# MC60.net
KiCad netlist of a schematic drawn in Altium Designer
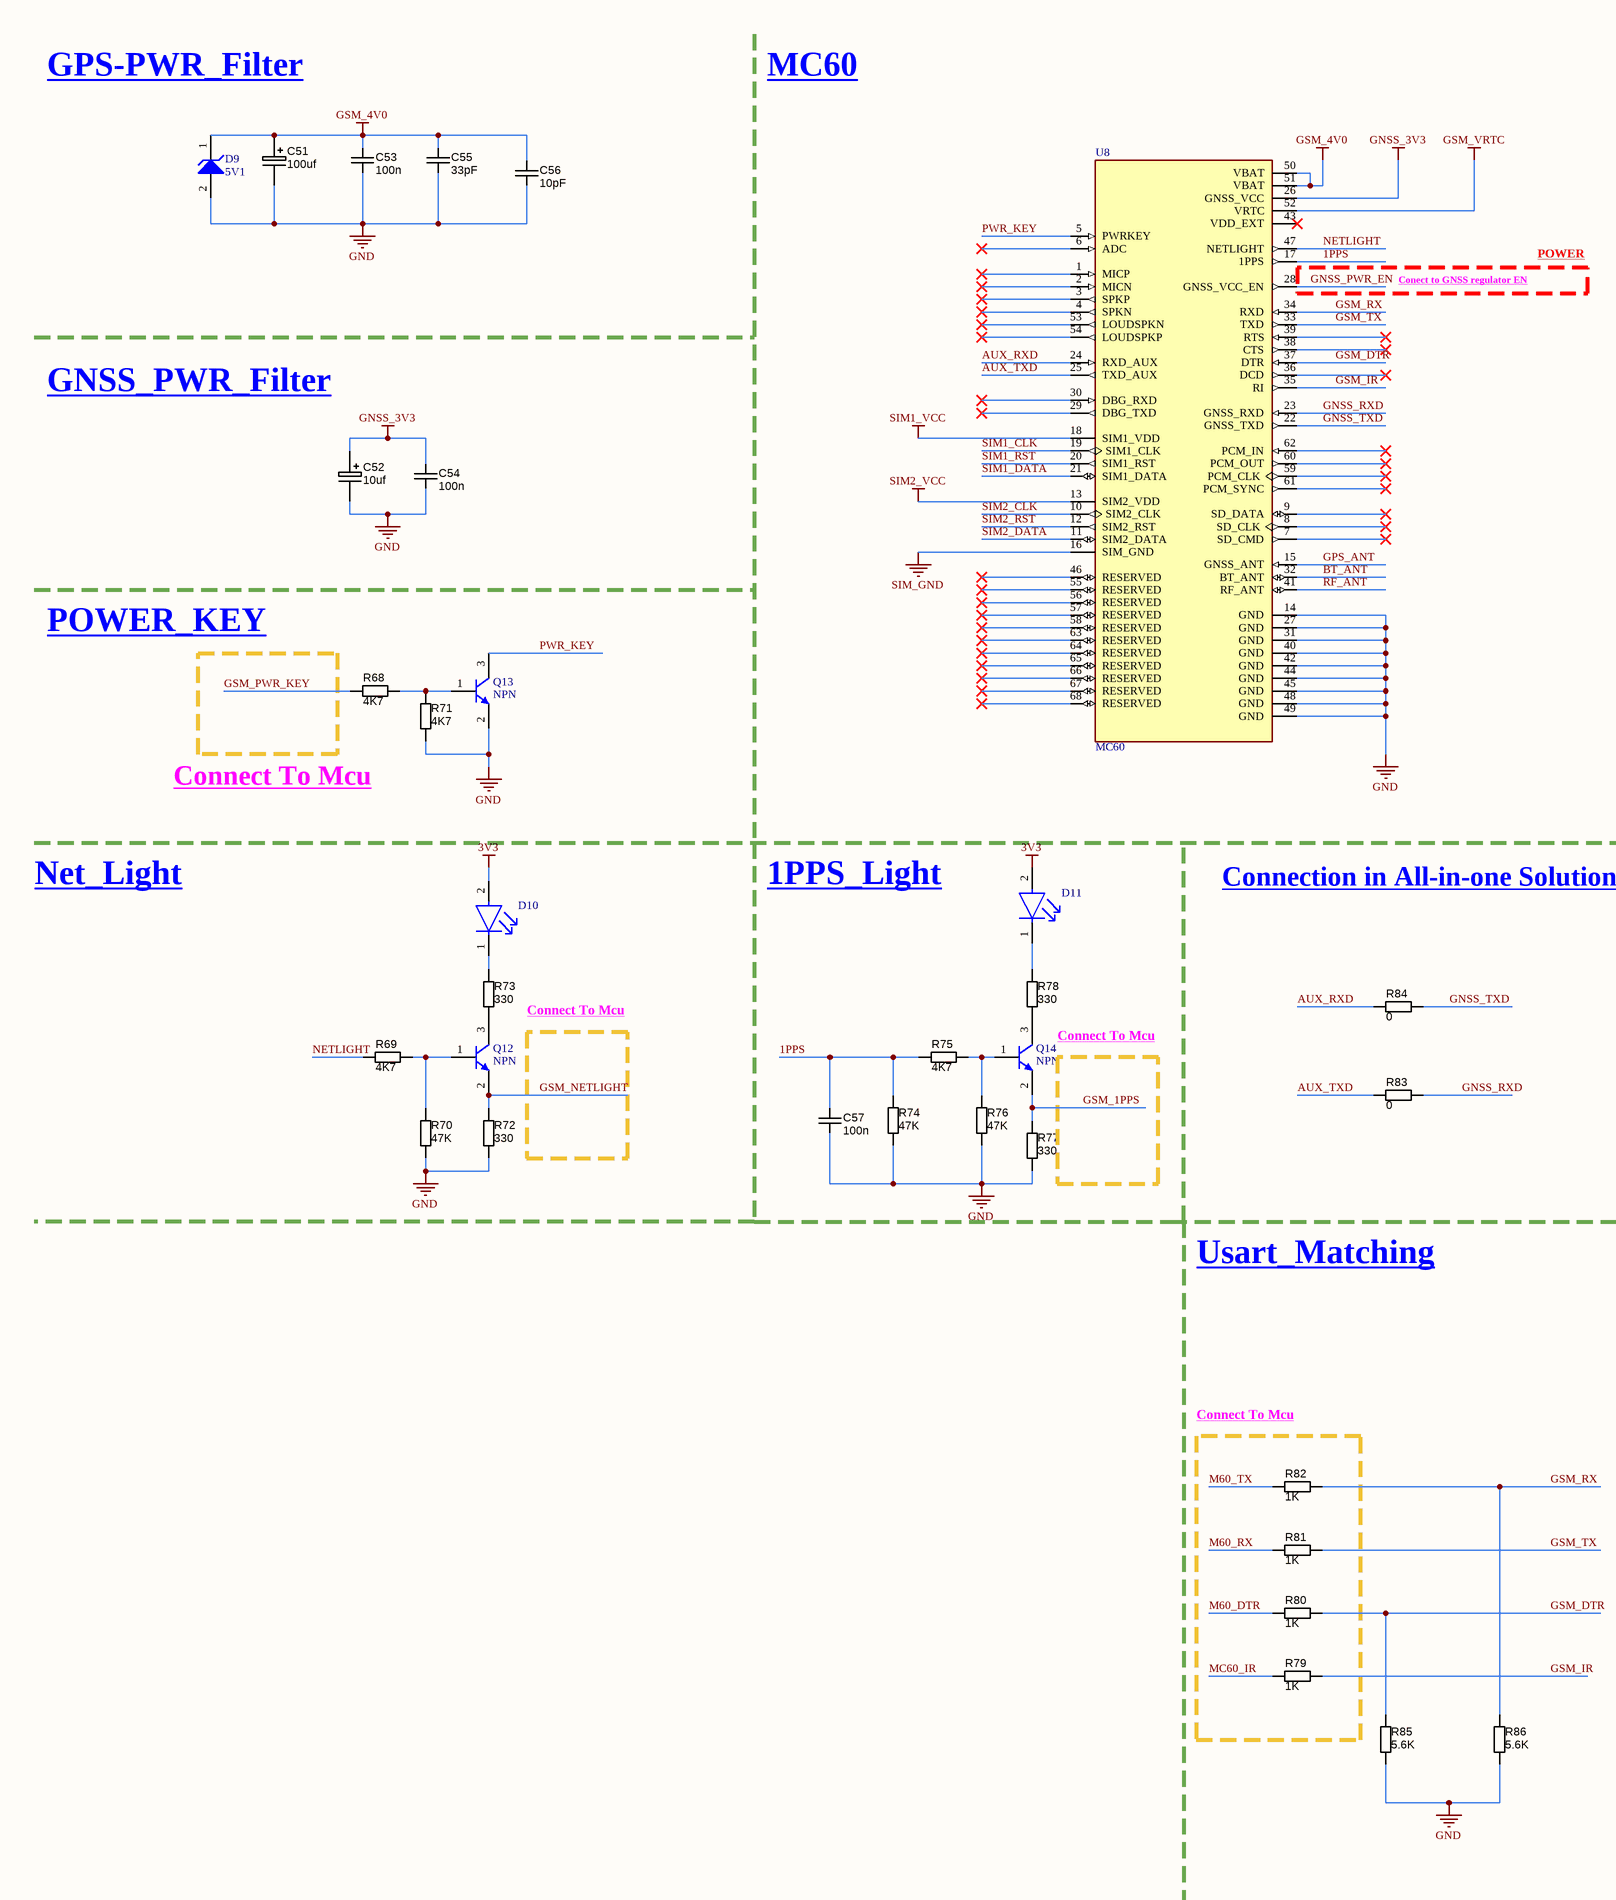
[diagram p0: MC60.SchDoc, left]
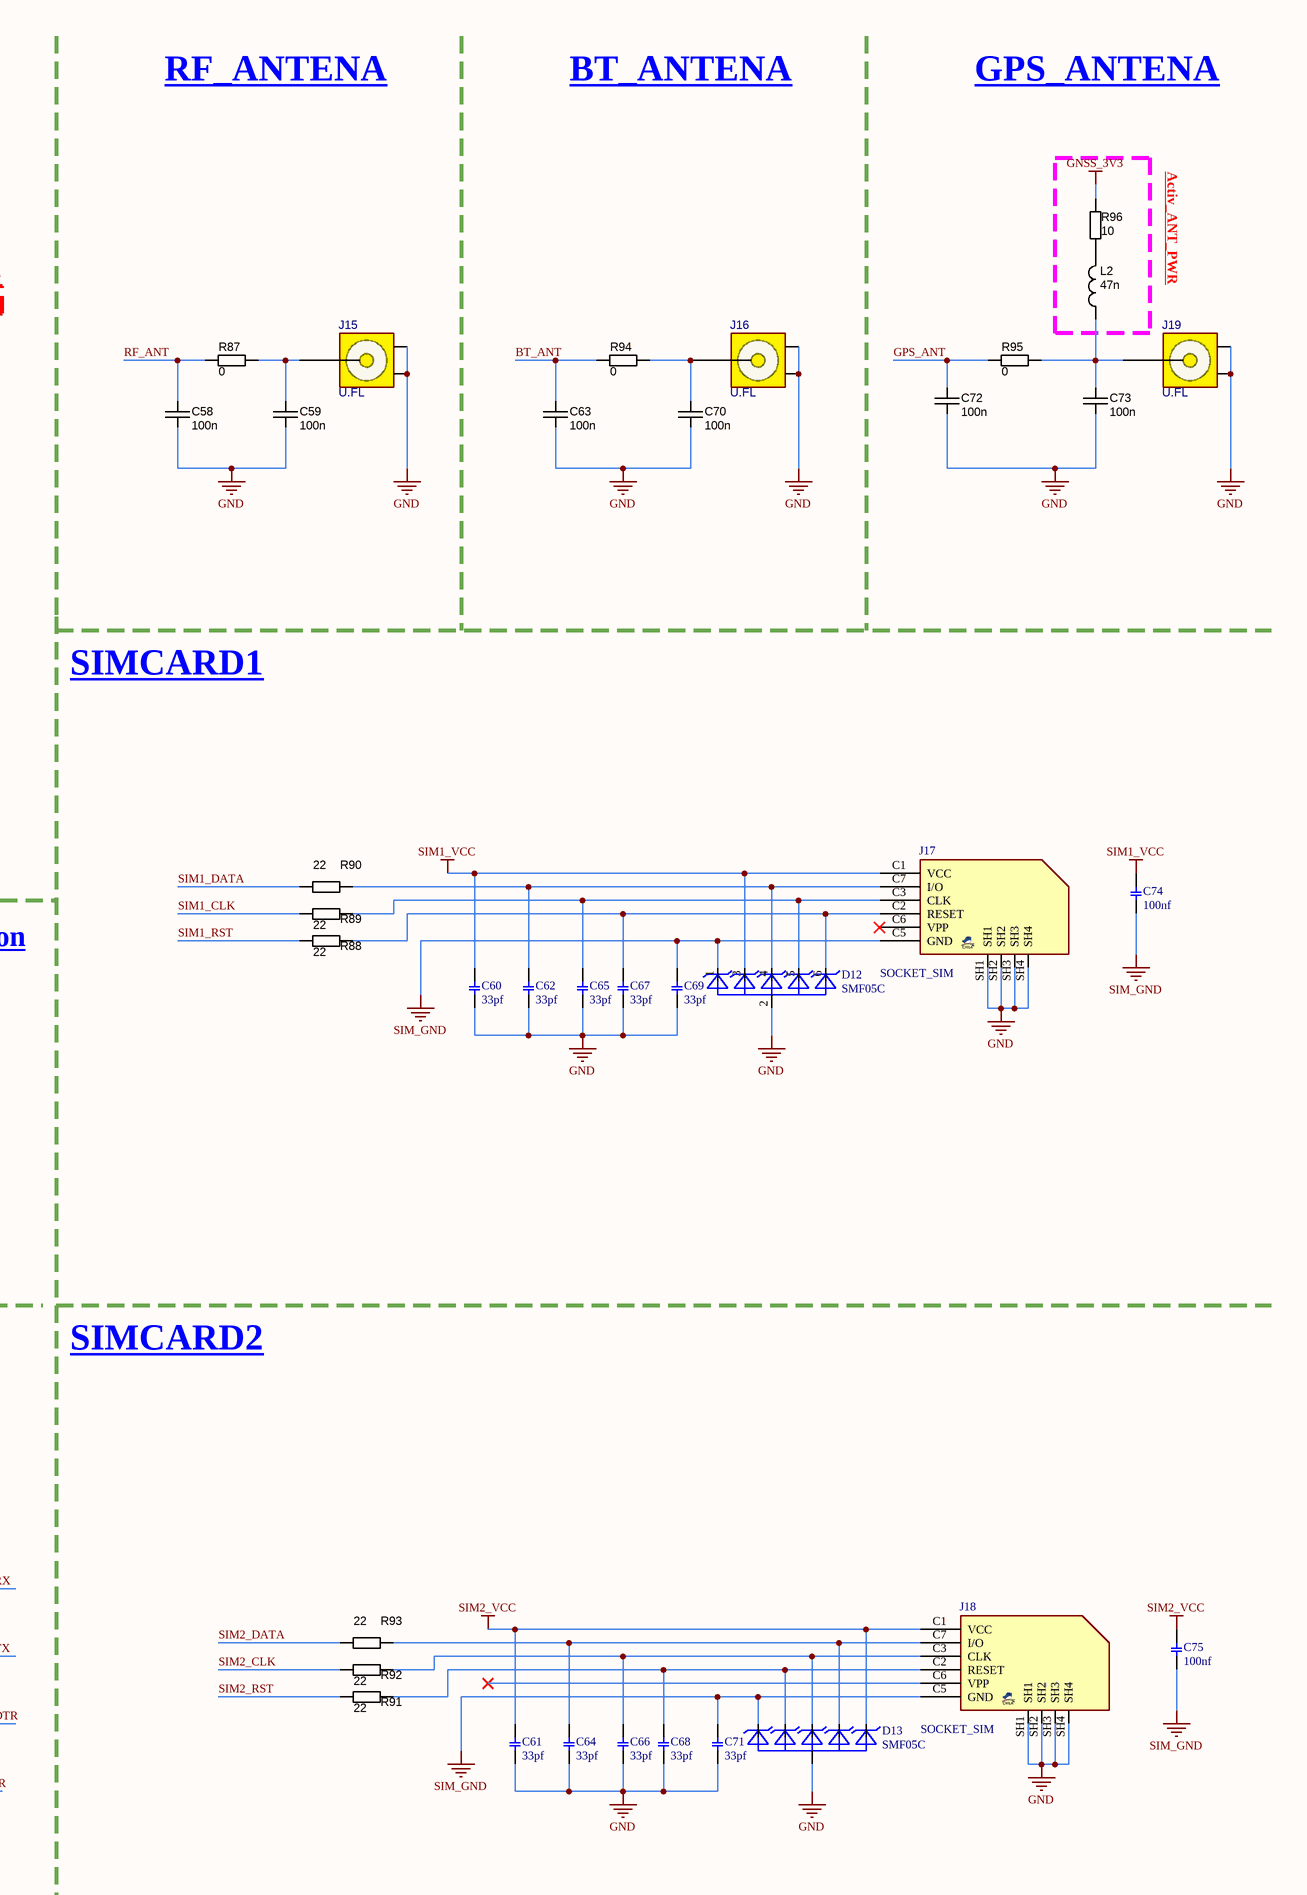
[diagram p1: MC60.SchDoc, right]

(export (version "E")
  (design (tool "Eeschema 10.0.6"))
  (components
    (comp (ref "C51")
      (value "100uf")
      (footprint "C_TN_3528")
      (description "Capacitor SMD Tantalum 100uF 10% 16V 3216-18")
      (fields (field (name "TOLERANCE") "±10%"))
      (libsource (lib "PBL - Capacitors") (part "CAPT_4u7_3216_16V"))
    )
    (comp (ref "C52")
      (value "10uf")
      (footprint "C_TN_3528")
      (description "Capacitor SMD Tantalum 10uF 10% 16V 3216-18")
      (fields (field (name "TOLERANCE") "±10%"))
      (libsource (lib "PBL - Capacitors") (part "CAPT_4u7_3216_16V"))
    )
    (comp (ref "C53")
      (value "100n")
      (footprint "CAPC1608X90N")
      (description "Capacitor SMD Cer 100nF 10% 50V X7R 0603")
      (fields (field (name "TOLERANCE") "±10%") (field (name "Comment") "approved sub OK"))
      (libsource (lib "PBL - Capacitors") (part "CAPC_100n_0603_X7R_50V_10%"))
    )
    (comp (ref "C54")
      (value "100n")
      (footprint "CAPC1608X90N")
      (description "Capacitor SMD Cer 100nF 10% 50V X7R 0603")
      (fields (field (name "TOLERANCE") "±10%") (field (name "Comment") "approved sub OK"))
      (libsource (lib "PBL - Capacitors") (part "CAPC_100n_0603_X7R_50V_10%"))
    )
    (comp (ref "C55")
      (value "33pF")
      (footprint "CAPC1608X90N")
      (description "Capacitor SMD Cer 33pF10% 50V X7R 0603")
      (fields (field (name "TOLERANCE") "±10%") (field (name "Comment") "approved sub OK"))
      (libsource (lib "PBL - Capacitors") (part "CAPC_100n_0603_X7R_50V_10%"))
    )
    (comp (ref "C56")
      (value "10pF")
      (footprint "CAPC1608X90N")
      (description "Capacitor SMD Cer 10pF10% 50V X7R 0603")
      (fields (field (name "TOLERANCE") "±10%") (field (name "Comment") "approved sub OK"))
      (libsource (lib "PBL - Capacitors") (part "CAPC_100n_0603_X7R_50V_10%"))
    )
    (comp (ref "C57")
      (value "100n")
      (footprint "CAPC1608X90N")
      (description "Capacitor SMD Cer 100nF 10% 50V X7R 0603")
      (fields (field (name "TOLERANCE") "±10%") (field (name "Comment") "approved sub OK"))
      (libsource (lib "PBL - Capacitors") (part "CAPC_100n_0603_X7R_50V_10%"))
    )
    (comp (ref "C58")
      (value "100n")
      (footprint "C0402")
      (description "Capacitor SMD Cer 100nF 10% 50V X7R 0603")
      (fields (field (name "TOLERANCE") "±10%") (field (name "Comment") "approved sub OK"))
      (libsource (lib "PBL - Capacitors") (part "CAPC_100n_0603_X7R_50V_10%"))
    )
    (comp (ref "C59")
      (value "100n")
      (footprint "C0402")
      (description "Capacitor SMD Cer 100nF 10% 50V X7R 0603")
      (fields (field (name "TOLERANCE") "±10%") (field (name "Comment") "approved sub OK"))
      (libsource (lib "PBL - Capacitors") (part "CAPC_100n_0603_X7R_50V_10%"))
    )
    (comp (ref "C60")
      (value "33pf")
      (footprint "0603")
      (description "Capacitor C SMD 0603")
      (libsource (lib "Capacitor") (part "Capacitor C SMD 0603"))
    )
    (comp (ref "C61")
      (value "33pf")
      (footprint "0603")
      (description "Capacitor C SMD 0603")
      (libsource (lib "Capacitor") (part "Capacitor C SMD 0603"))
    )
    (comp (ref "C62")
      (value "33pf")
      (footprint "0603")
      (description "Capacitor C SMD 0603")
      (libsource (lib "Capacitor") (part "Capacitor C SMD 0603"))
    )
    (comp (ref "C63")
      (value "100n")
      (footprint "C0402")
      (description "Capacitor SMD Cer 100nF 10% 50V X7R 0603")
      (fields (field (name "TOLERANCE") "±10%") (field (name "Comment") "approved sub OK"))
      (libsource (lib "PBL - Capacitors") (part "CAPC_100n_0603_X7R_50V_10%"))
    )
    (comp (ref "C64")
      (value "33pf")
      (footprint "0603")
      (description "Capacitor C SMD 0603")
      (libsource (lib "Capacitor") (part "Capacitor C SMD 0603"))
    )
    (comp (ref "C65")
      (value "33pf")
      (footprint "0603")
      (description "Capacitor C SMD 0603")
      (libsource (lib "Capacitor") (part "Capacitor C SMD 0603"))
    )
    (comp (ref "C66")
      (value "33pf")
      (footprint "0603")
      (description "Capacitor C SMD 0603")
      (libsource (lib "Capacitor") (part "Capacitor C SMD 0603"))
    )
    (comp (ref "C67")
      (value "33pf")
      (footprint "0603")
      (description "Capacitor C SMD 0603")
      (libsource (lib "Capacitor") (part "Capacitor C SMD 0603"))
    )
    (comp (ref "C68")
      (value "33pf")
      (footprint "0603")
      (description "Capacitor C SMD 0603")
      (libsource (lib "Capacitor") (part "Capacitor C SMD 0603"))
    )
    (comp (ref "C69")
      (value "33pf")
      (footprint "0603")
      (description "Capacitor C SMD 0603")
      (libsource (lib "Capacitor") (part "Capacitor C SMD 0603"))
    )
    (comp (ref "C70")
      (value "100n")
      (footprint "C0402")
      (description "Capacitor SMD Cer 100nF 10% 50V X7R 0603")
      (fields (field (name "TOLERANCE") "±10%") (field (name "Comment") "approved sub OK"))
      (libsource (lib "PBL - Capacitors") (part "CAPC_100n_0603_X7R_50V_10%"))
    )
    (comp (ref "C71")
      (value "33pf")
      (footprint "0603")
      (description "Capacitor C SMD 0603")
      (libsource (lib "Capacitor") (part "Capacitor C SMD 0603"))
    )
    (comp (ref "C72")
      (value "100n")
      (footprint "C0402")
      (description "Capacitor SMD Cer 100nF 10% 50V X7R 0603")
      (fields (field (name "TOLERANCE") "±10%") (field (name "Comment") "approved sub OK"))
      (libsource (lib "PBL - Capacitors") (part "CAPC_100n_0603_X7R_50V_10%"))
    )
    (comp (ref "C73")
      (value "100n")
      (footprint "C0402")
      (description "Capacitor SMD Cer 100nF 10% 50V X7R 0603")
      (fields (field (name "TOLERANCE") "±10%") (field (name "Comment") "approved sub OK"))
      (libsource (lib "PBL - Capacitors") (part "CAPC_100n_0603_X7R_50V_10%"))
    )
    (comp (ref "C74")
      (value "100nf")
      (footprint "0603")
      (description "Capacitor C SMD 0603")
      (libsource (lib "Capacitor") (part "Capacitor C SMD 0603"))
    )
    (comp (ref "C75")
      (value "100nf")
      (footprint "0603")
      (description "Capacitor C SMD 0603")
      (libsource (lib "Capacitor") (part "Capacitor C SMD 0603"))
    )
    (comp (ref "D9")
      (value "5V1")
      (footprint "ONSC-SMA-2-403D-02_F_V")
      (description "1.5 W Zener Voltage Regulator, 2-Pin SMA, Pb-Free, Tape and Reel")
      (fields (field (name "MANUFACTURER") "On Semiconductor") (field (name "PARTNUMBER") "1SMA5939BT3G"))
      (libsource (lib "Altium Content Vault") (part "ONSC-K1A2-2"))
    )
    (comp (ref "D10")
      (value "LTST-C191TBKT")
      (footprint "FP-LTST-C191TBKT-MFG")
      (description "LED BLUE CLEAR CHIP SMD")
      (libsource (lib "Altium Content Vault") (part "8706943c75ba83719d021d2fdc84c58"))
    )
    (comp (ref "D11")
      (value "LTST-C191TBKT")
      (footprint "FP-LTST-C191TBKT-MFG")
      (description "LED BLUE CLEAR CHIP SMD")
      (libsource (lib "Altium Content Vault") (part "8706943c75ba83719d021d2fdc84c58"))
    )
    (comp (ref "D12")
      (value "SMF05C")
      (footprint "SC70-6")
      (description "12.5V Clamp 8A _8/20Âµs_ Ipp Tvs Diode Surface Mount SC-88/SC70-6/SOT-363")
      (fields (field (name "MF") "ON Semiconductor"))
      (libsource (lib "") (part "SMF05C_1"))
    )
    (comp (ref "D13")
      (value "SMF05C")
      (footprint "SC70-6")
      (description "12.5V Clamp 8A _8/20Âµs_ Ipp Tvs Diode Surface Mount SC-88/SC70-6/SOT-363")
      (fields (field (name "MF") "ON Semiconductor"))
      (libsource (lib "SMF05C") (part "SMF05C"))
    )
    (comp (ref "J15")
      (value "U.FL")
      (footprint "UFL")
      (description "CONN, RF, U.FL, STRAIGHT, Ultra Miniature Coaxial")
      (fields
        (field (name "MANF_P#") "CONUFL001-SMD, U.FL-R-SMT-1(10), 128-0711-201")
        (field (name "MANF") "Linx, Hirose, Cinch")
      )
      (libsource (lib "conn_rf") (part "CONN_RF_UFL"))
    )
    (comp (ref "J16")
      (value "U.FL")
      (footprint "UFL")
      (description "CONN, RF, U.FL, STRAIGHT, Ultra Miniature Coaxial")
      (fields
        (field (name "MANF_P#") "CONUFL001-SMD, U.FL-R-SMT-1(10), 128-0711-201")
        (field (name "MANF") "Linx, Hirose, Cinch")
      )
      (libsource (lib "conn_rf") (part "CONN_RF_UFL"))
    )
    (comp (ref "J17")
      (value "SOCKET_SIM")
      (footprint "SIM_MICRO_GCT")
      (description "SOCKET, SIM MICRO")
      (libsource (lib "socket_card") (part "SIM_MICRO_6"))
    )
    (comp (ref "J18")
      (value "SOCKET_SIM")
      (footprint "SIM_MICRO_GCT")
      (description "SOCKET, SIM MICRO")
      (libsource (lib "socket_card") (part "SIM_MICRO_6"))
    )
    (comp (ref "J19")
      (value "U.FL")
      (footprint "UFL")
      (description "CONN, RF, U.FL, STRAIGHT, Ultra Miniature Coaxial")
      (fields
        (field (name "MANF_P#") "CONUFL001-SMD, U.FL-R-SMT-1(10), 128-0711-201")
        (field (name "MANF") "Linx, Hirose, Cinch")
      )
      (libsource (lib "conn_rf") (part "CONN_RF_UFL"))
    )
    (comp (ref "L2")
      (value "47n")
      (footprint "L0603")
      (description "Inductor SMD Low DCR 47 nH 900mA 20% 1210")
      (fields (field (name "TOLERANCE") "±20%"))
      (libsource (lib "PBL - Inductors") (part "INDC_10u_LowRDC"))
    )
    (comp (ref "Q12")
      (value "NPN")
      (footprint "SOT23-3")
      (description "NPN Bipolar Transistor")
      (fields (field (name "PUBLISHER") "Altium Limited"))
      (libsource (lib "Miscellaneous Devices") (part "NPN"))
    )
    (comp (ref "Q13")
      (value "NPN")
      (footprint "SOT23-3")
      (description "NPN Bipolar Transistor")
      (fields (field (name "PUBLISHER") "Altium Limited"))
      (libsource (lib "Miscellaneous Devices") (part "NPN"))
    )
    (comp (ref "Q14")
      (value "NPN")
      (footprint "SOT23-3")
      (description "NPN Bipolar Transistor")
      (fields (field (name "PUBLISHER") "Altium Limited"))
      (libsource (lib "Miscellaneous Devices") (part "NPN"))
    )
    (comp (ref "R68")
      (value "4K7")
      (footprint "RESC1608X55N")
      (description "Resistor SMD chip 4.7k Ohm 0.1W 5% 0603")
      (fields (field (name "TOLERANCE") "±5%") (field (name "Comment") "Thick Film"))
      (libsource (lib "PBL - Resistors") (part "RES_4K7_0603_5%"))
    )
    (comp (ref "R69")
      (value "4K7")
      (footprint "RESC1608X55N")
      (description "Resistor SMD chip 4.7k Ohm 0.1W 5% 0603")
      (fields (field (name "TOLERANCE") "±5%") (field (name "Comment") "Thick Film"))
      (libsource (lib "") (part "RES_4K7_0603_5%_2"))
    )
    (comp (ref "R70")
      (value "47K")
      (footprint "RESC1608X55N")
      (description "Resistor SMD chip 47K Ohm 0.1W 5% 0603")
      (fields (field (name "TOLERANCE") "±5%") (field (name "Comment") "Thick Film"))
      (libsource (lib "") (part "RES_4K7_0603_5%_1"))
    )
    (comp (ref "R71")
      (value "4K7")
      (footprint "RESC1608X55N")
      (description "Resistor SMD chip 4.7k Ohm 0.1W 5% 0603")
      (fields (field (name "TOLERANCE") "±5%") (field (name "Comment") "Thick Film"))
      (libsource (lib "") (part "RES_4K7_0603_5%_1"))
    )
    (comp (ref "R72")
      (value "330")
      (footprint "RESC1608X55N")
      (description "Resistor SMD chip 330 Ohm 0.1W 5% 0603")
      (fields (field (name "TOLERANCE") "±5%") (field (name "Comment") "Thick Film"))
      (libsource (lib "") (part "RES_4K7_0603_5%_1"))
    )
    (comp (ref "R73")
      (value "330")
      (footprint "RESC1608X55N")
      (description "Resistor SMD chip 330 Ohm 0.1W 5% 0603")
      (fields (field (name "TOLERANCE") "±5%") (field (name "Comment") "Thick Film"))
      (libsource (lib "") (part "RES_4K7_0603_5%_1"))
    )
    (comp (ref "R74")
      (value "47K")
      (footprint "RESC1608X55N")
      (description "Resistor SMD chip 47K Ohm 0.1W 5% 0603")
      (fields (field (name "TOLERANCE") "±5%") (field (name "Comment") "Thick Film"))
      (libsource (lib "") (part "RES_4K7_0603_5%_1"))
    )
    (comp (ref "R75")
      (value "4K7")
      (footprint "RESC1608X55N")
      (description "Resistor SMD chip 4.7k Ohm 0.1W 5% 0603")
      (fields (field (name "TOLERANCE") "±5%") (field (name "Comment") "Thick Film"))
      (libsource (lib "") (part "RES_4K7_0603_5%_2"))
    )
    (comp (ref "R76")
      (value "47K")
      (footprint "RESC1608X55N")
      (description "Resistor SMD chip 47K Ohm 0.1W 5% 0603")
      (fields (field (name "TOLERANCE") "±5%") (field (name "Comment") "Thick Film"))
      (libsource (lib "") (part "RES_4K7_0603_5%_1"))
    )
    (comp (ref "R77")
      (value "330")
      (footprint "RESC1608X55N")
      (description "Resistor SMD chip 330 Ohm 0.1W 5% 0603")
      (fields (field (name "TOLERANCE") "±5%") (field (name "Comment") "Thick Film"))
      (libsource (lib "") (part "RES_4K7_0603_5%_1"))
    )
    (comp (ref "R78")
      (value "330")
      (footprint "RESC1608X55N")
      (description "Resistor SMD chip 330 Ohm 0.1W 5% 0603")
      (fields (field (name "TOLERANCE") "±5%") (field (name "Comment") "Thick Film"))
      (libsource (lib "") (part "RES_4K7_0603_5%_1"))
    )
    (comp (ref "R79")
      (value "1K")
      (footprint "RESC1608X55N")
      (description "Resistor SMD chip 1K Ohm 0.1W 5% 0603")
      (fields (field (name "TOLERANCE") "±5%") (field (name "Comment") "Thick Film"))
      (libsource (lib "PBL - Resistors") (part "RES_4K7_0603_5%"))
    )
    (comp (ref "R80")
      (value "1K")
      (footprint "RESC1608X55N")
      (description "Resistor SMD chip 1K Ohm 0.1W 5% 0603")
      (fields (field (name "TOLERANCE") "±5%") (field (name "Comment") "Thick Film"))
      (libsource (lib "PBL - Resistors") (part "RES_4K7_0603_5%"))
    )
    (comp (ref "R81")
      (value "1K")
      (footprint "RESC1608X55N")
      (description "Resistor SMD chip 1K Ohm 0.1W 5% 0603")
      (fields (field (name "TOLERANCE") "±5%") (field (name "Comment") "Thick Film"))
      (libsource (lib "PBL - Resistors") (part "RES_4K7_0603_5%"))
    )
    (comp (ref "R82")
      (value "1K")
      (footprint "RESC1608X55N")
      (description "Resistor SMD chip 1K Ohm 0.1W 5% 0603")
      (fields (field (name "TOLERANCE") "±5%") (field (name "Comment") "Thick Film"))
      (libsource (lib "PBL - Resistors") (part "RES_4K7_0603_5%"))
    )
    (comp (ref "R83")
      (value "0")
      (footprint "RESC1608X55N")
      (description "Resistor SMD chip 0 Ohm 0.1W 5% 0603")
      (fields (field (name "TOLERANCE") "±5%") (field (name "Comment") "Thick Film"))
      (libsource (lib "PBL - Resistors") (part "RES_4K7_0603_5%"))
    )
    (comp (ref "R84")
      (value "0")
      (footprint "RESC1608X55N")
      (description "Resistor SMD chip 0 Ohm 0.1W 5% 0603")
      (fields (field (name "TOLERANCE") "±5%") (field (name "Comment") "Thick Film"))
      (libsource (lib "PBL - Resistors") (part "RES_4K7_0603_5%"))
    )
    (comp (ref "R85")
      (value "5.6K")
      (footprint "RESC1608X55N")
      (description "Resistor SMD chip 5.6K Ohm 0.1W 5% 0603")
      (fields (field (name "TOLERANCE") "±5%") (field (name "Comment") "Thick Film"))
      (libsource (lib "") (part "RES_4K7_0603_5%_1"))
    )
    (comp (ref "R86")
      (value "5.6K")
      (footprint "RESC1608X55N")
      (description "Resistor SMD chip 5.6K Ohm 0.1W 5% 0603")
      (fields (field (name "TOLERANCE") "±5%") (field (name "Comment") "Thick Film"))
      (libsource (lib "") (part "RES_4K7_0603_5%_1"))
    )
    (comp (ref "R87")
      (value "0")
      (footprint "0402")
      (description "Resistor SMD chip 0 Ohm 0.1W 5% 0603")
      (fields (field (name "TOLERANCE") "±5%") (field (name "Comment") "Thick Film"))
      (libsource (lib "PBL - Resistors") (part "RES_4K7_0603_5%"))
    )
    (comp (ref "R88")
      (value "22")
      (footprint "RESC1608X55N")
      (description "Resistor SMD chip 22 Ohm 0.1W 5% 0603")
      (fields (field (name "TOLERANCE") "±5%") (field (name "Comment") "Thick Film"))
      (libsource (lib "") (part "RES_4K7_0603_5%_2"))
    )
    (comp (ref "R89")
      (value "22")
      (footprint "RESC1608X55N")
      (description "Resistor SMD chip 22 Ohm 0.1W 5% 0603")
      (fields (field (name "TOLERANCE") "±5%") (field (name "Comment") "Thick Film"))
      (libsource (lib "") (part "RES_4K7_0603_5%_2"))
    )
    (comp (ref "R90")
      (value "22")
      (footprint "RESC1608X55N")
      (description "Resistor SMD chip 22 Ohm 0.1W 5% 0603")
      (fields (field (name "TOLERANCE") "±5%") (field (name "Comment") "Thick Film"))
      (libsource (lib "") (part "RES_4K7_0603_5%_2"))
    )
    (comp (ref "R91")
      (value "22")
      (footprint "RESC1608X55N")
      (description "Resistor SMD chip 22 Ohm 0.1W 5% 0603")
      (fields (field (name "TOLERANCE") "±5%") (field (name "Comment") "Thick Film"))
      (libsource (lib "") (part "RES_4K7_0603_5%_2"))
    )
    (comp (ref "R92")
      (value "22")
      (footprint "RESC1608X55N")
      (description "Resistor SMD chip 22 Ohm 0.1W 5% 0603")
      (fields (field (name "TOLERANCE") "±5%") (field (name "Comment") "Thick Film"))
      (libsource (lib "") (part "RES_4K7_0603_5%_2"))
    )
    (comp (ref "R93")
      (value "22")
      (footprint "RESC1608X55N")
      (description "Resistor SMD chip 22 Ohm 0.1W 5% 0603")
      (fields (field (name "TOLERANCE") "±5%") (field (name "Comment") "Thick Film"))
      (libsource (lib "") (part "RES_4K7_0603_5%_2"))
    )
    (comp (ref "R94")
      (value "0")
      (footprint "0402")
      (description "Resistor SMD chip 0 Ohm 0.1W 5% 0603")
      (fields (field (name "TOLERANCE") "±5%") (field (name "Comment") "Thick Film"))
      (libsource (lib "PBL - Resistors") (part "RES_4K7_0603_5%"))
    )
    (comp (ref "R95")
      (value "0")
      (footprint "0402")
      (description "Resistor SMD chip 0 Ohm 0.1W 5% 0603")
      (fields (field (name "TOLERANCE") "±5%") (field (name "Comment") "Thick Film"))
      (libsource (lib "PBL - Resistors") (part "RES_4K7_0603_5%"))
    )
    (comp (ref "R96")
      (value "10")
      (footprint "0402")
      (description "Resistor SMD chip 10 Ohm 0.1W 5% 0603")
      (fields (field (name "TOLERANCE") "±5%") (field (name "Comment") "Thick Film"))
      (libsource (lib "") (part "RES_4K7_0603_5%_1"))
    )
    (comp (ref "U8")
      (value "MC60")
      (footprint "XCVR_MC60")
      (fields (field (name "MF") "Quectel"))
      (libsource (lib "MC60") (part "MC60"))
    )
  )
  (nets
    (net (code "1") (name "/1PPS") (class "Default")
      (node (ref "C57") (pin "1") (pintype "passive"))
      (node (ref "R74") (pin "1") (pinfunction "1_1") (pintype "passive"))
      (node (ref "R75") (pin "1") (pinfunction "1_1") (pintype "passive"))
      (node (ref "U8") (pin "17") (pinfunction "1PPS_17") (pintype "output"))
    )
    (net (code "2") (name "/AUX_RXD") (class "Default")
      (node (ref "R84") (pin "2") (pinfunction "2_2") (pintype "passive"))
      (node (ref "U8") (pin "24") (pinfunction "RXD_AUX_24") (pintype "input"))
    )
    (net (code "3") (name "/AUX_TXD") (class "Default")
      (node (ref "R83") (pin "2") (pinfunction "2_2") (pintype "passive"))
      (node (ref "U8") (pin "25") (pinfunction "TXD_AUX_25") (pintype "output"))
    )
    (net (code "4") (name "/BT_ANT") (class "Default")
      (node (ref "C63") (pin "1") (pintype "passive"))
      (node (ref "R94") (pin "2") (pinfunction "2_2") (pintype "passive"))
      (node (ref "U8") (pin "32") (pinfunction "BT_ANT_32") (pintype "bidirectional"))
    )
    (net (code "5") (name "/GNSS_PWR_EN") (class "Default")
      (node (ref "U8") (pin "28") (pinfunction "GNSS_VCC_EN_28") (pintype "output"))
    )
    (net (code "6") (name "/GNSS_RXD") (class "Default")
      (node (ref "R83") (pin "1") (pinfunction "1_1") (pintype "passive"))
      (node (ref "U8") (pin "23") (pinfunction "GNSS_RXD_23") (pintype "input"))
    )
    (net (code "7") (name "/GNSS_TXD") (class "Default")
      (node (ref "R84") (pin "1") (pinfunction "1_1") (pintype "passive"))
      (node (ref "U8") (pin "22") (pinfunction "GNSS_TXD_22") (pintype "output"))
    )
    (net (code "8") (name "/GPS_ANT") (class "Default")
      (node (ref "C72") (pin "1") (pintype "passive"))
      (node (ref "R95") (pin "2") (pinfunction "2_2") (pintype "passive"))
      (node (ref "U8") (pin "15") (pinfunction "GNSS_ANT_15") (pintype "input"))
    )
    (net (code "9") (name "/GSM_1PPS") (class "Default")
      (node (ref "Q14") (pin "2") (pinfunction "E_2") (pintype "passive"))
      (node (ref "R77") (pin "1") (pinfunction "1_1") (pintype "passive"))
    )
    (net (code "10") (name "/GSM_DTR") (class "Default")
      (node (ref "R80") (pin "1") (pinfunction "1_1") (pintype "passive"))
      (node (ref "R85") (pin "1") (pinfunction "1_1") (pintype "passive"))
      (node (ref "U8") (pin "37") (pinfunction "DTR_37") (pintype "input"))
    )
    (net (code "11") (name "/GSM_IR") (class "Default")
      (node (ref "R79") (pin "1") (pinfunction "1_1") (pintype "passive"))
      (node (ref "U8") (pin "35") (pinfunction "RI_35") (pintype "output"))
    )
    (net (code "12") (name "/GSM_NETLIGHT") (class "Default")
      (node (ref "Q12") (pin "2") (pinfunction "E_2") (pintype "passive"))
      (node (ref "R72") (pin "1") (pinfunction "1_1") (pintype "passive"))
    )
    (net (code "13") (name "/GSM_PWR_KEY") (class "Default")
      (node (ref "R68") (pin "2") (pinfunction "2_2") (pintype "passive"))
    )
    (net (code "14") (name "/GSM_RX") (class "Default")
      (node (ref "R82") (pin "1") (pinfunction "1_1") (pintype "passive"))
      (node (ref "R86") (pin "1") (pinfunction "1_1") (pintype "passive"))
      (node (ref "U8") (pin "34") (pinfunction "RXD_34") (pintype "input"))
    )
    (net (code "15") (name "/GSM_TX") (class "Default")
      (node (ref "R81") (pin "1") (pinfunction "1_1") (pintype "passive"))
      (node (ref "U8") (pin "33") (pinfunction "TXD_33") (pintype "output"))
    )
    (net (code "16") (name "/M60_DTR") (class "Default")
      (node (ref "R80") (pin "2") (pinfunction "2_2") (pintype "passive"))
    )
    (net (code "17") (name "/M60_RX") (class "Default")
      (node (ref "R81") (pin "2") (pinfunction "2_2") (pintype "passive"))
    )
    (net (code "18") (name "/M60_TX") (class "Default")
      (node (ref "R82") (pin "2") (pinfunction "2_2") (pintype "passive"))
    )
    (net (code "19") (name "/MC60_IR") (class "Default")
      (node (ref "R79") (pin "2") (pinfunction "2_2") (pintype "passive"))
    )
    (net (code "20") (name "/NETLIGHT") (class "Default")
      (node (ref "R69") (pin "1") (pinfunction "1_1") (pintype "passive"))
      (node (ref "U8") (pin "47") (pinfunction "NETLIGHT_47") (pintype "output"))
    )
    (net (code "21") (name "/PWR_KEY") (class "Default")
      (node (ref "Q13") (pin "3") (pinfunction "C_3") (pintype "passive"))
      (node (ref "U8") (pin "5") (pinfunction "PWRKEY_5") (pintype "input"))
    )
    (net (code "22") (name "/RF_ANT") (class "Default")
      (node (ref "C58") (pin "1") (pintype "passive"))
      (node (ref "R87") (pin "2") (pinfunction "2_2") (pintype "passive"))
      (node (ref "U8") (pin "41") (pinfunction "RF_ANT_41") (pintype "bidirectional"))
    )
    (net (code "23") (name "/SIM1_CLK") (class "Default")
      (node (ref "R89") (pin "1") (pinfunction "1_1") (pintype "passive"))
      (node (ref "U8") (pin "19") (pinfunction "SIM1_CLK_19") (pintype "output"))
    )
    (net (code "24") (name "/SIM1_DATA") (class "Default")
      (node (ref "R90") (pin "1") (pinfunction "1_1") (pintype "passive"))
      (node (ref "U8") (pin "21") (pinfunction "SIM1_DATA_21") (pintype "bidirectional"))
    )
    (net (code "25") (name "/SIM1_RST") (class "Default")
      (node (ref "R88") (pin "1") (pinfunction "1_1") (pintype "passive"))
      (node (ref "U8") (pin "20") (pinfunction "SIM1_RST_20") (pintype "output"))
    )
    (net (code "26") (name "/SIM2_CLK") (class "Default")
      (node (ref "R92") (pin "1") (pinfunction "1_1") (pintype "passive"))
      (node (ref "U8") (pin "10") (pinfunction "SIM2_CLK_10") (pintype "output"))
    )
    (net (code "27") (name "/SIM2_DATA") (class "Default")
      (node (ref "R93") (pin "1") (pinfunction "1_1") (pintype "passive"))
      (node (ref "U8") (pin "11") (pinfunction "SIM2_DATA_11") (pintype "bidirectional"))
    )
    (net (code "28") (name "/SIM2_RST") (class "Default")
      (node (ref "R91") (pin "1") (pinfunction "1_1") (pintype "passive"))
      (node (ref "U8") (pin "12") (pinfunction "SIM2_RST_12") (pintype "output"))
    )
    (net (code "29") (name "3V3") (class "Default")
      (node (ref "D10") (pin "2") (pinfunction "A_2") (pintype "passive"))
      (node (ref "D11") (pin "2") (pinfunction "A_2") (pintype "passive"))
    )
    (net (code "30") (name "GND") (class "Default")
      (node (ref "C51") (pin "2") (pintype "passive"))
      (node (ref "C52") (pin "2") (pintype "passive"))
      (node (ref "C53") (pin "2") (pintype "passive"))
      (node (ref "C54") (pin "2") (pintype "passive"))
      (node (ref "C55") (pin "2") (pintype "passive"))
      (node (ref "C56") (pin "2") (pintype "passive"))
      (node (ref "C57") (pin "2") (pintype "passive"))
      (node (ref "C58") (pin "2") (pintype "passive"))
      (node (ref "C59") (pin "2") (pintype "passive"))
      (node (ref "C60") (pin "1") (pinfunction "1_1") (pintype "passive"))
      (node (ref "C61") (pin "1") (pinfunction "1_1") (pintype "passive"))
      (node (ref "C62") (pin "1") (pinfunction "1_1") (pintype "passive"))
      (node (ref "C63") (pin "2") (pintype "passive"))
      (node (ref "C64") (pin "1") (pinfunction "1_1") (pintype "passive"))
      (node (ref "C65") (pin "1") (pinfunction "1_1") (pintype "passive"))
      (node (ref "C66") (pin "1") (pinfunction "1_1") (pintype "passive"))
      (node (ref "C67") (pin "1") (pinfunction "1_1") (pintype "passive"))
      (node (ref "C68") (pin "1") (pinfunction "1_1") (pintype "passive"))
      (node (ref "C69") (pin "1") (pinfunction "1_1") (pintype "passive"))
      (node (ref "C70") (pin "2") (pintype "passive"))
      (node (ref "C71") (pin "1") (pinfunction "1_1") (pintype "passive"))
      (node (ref "C72") (pin "2") (pintype "passive"))
      (node (ref "C73") (pin "2") (pintype "passive"))
      (node (ref "D12") (pin "2") (pinfunction "A_2") (pintype "passive"))
      (node (ref "D13") (pin "2") (pinfunction "A_2") (pintype "passive"))
      (node (ref "D9") (pin "2") (pinfunction "A_2") (pintype "passive"))
      (node (ref "J15") (pin "2") (pinfunction "G1_2") (pintype "passive"))
      (node (ref "J15") (pin "3") (pinfunction "G2_3") (pintype "passive"))
      (node (ref "J16") (pin "2") (pinfunction "G1_2") (pintype "passive"))
      (node (ref "J16") (pin "3") (pinfunction "G2_3") (pintype "passive"))
      (node (ref "J17") (pin "SH1") (pinfunction "SH1_SH1") (pintype "passive"))
      (node (ref "J17") (pin "SH2") (pinfunction "SH2_SH2") (pintype "passive"))
      (node (ref "J17") (pin "SH3") (pinfunction "SH3_SH3") (pintype "passive"))
      (node (ref "J17") (pin "SH4") (pinfunction "SH4_SH4") (pintype "passive"))
      (node (ref "J18") (pin "SH1") (pinfunction "SH1_SH1") (pintype "passive"))
      (node (ref "J18") (pin "SH2") (pinfunction "SH2_SH2") (pintype "passive"))
      (node (ref "J18") (pin "SH3") (pinfunction "SH3_SH3") (pintype "passive"))
      (node (ref "J18") (pin "SH4") (pinfunction "SH4_SH4") (pintype "passive"))
      (node (ref "J19") (pin "2") (pinfunction "G1_2") (pintype "passive"))
      (node (ref "J19") (pin "3") (pinfunction "G2_3") (pintype "passive"))
      (node (ref "Q13") (pin "2") (pinfunction "E_2") (pintype "passive"))
      (node (ref "R70") (pin "2") (pinfunction "2_2") (pintype "passive"))
      (node (ref "R71") (pin "2") (pinfunction "2_2") (pintype "passive"))
      (node (ref "R72") (pin "2") (pinfunction "2_2") (pintype "passive"))
      (node (ref "R74") (pin "2") (pinfunction "2_2") (pintype "passive"))
      (node (ref "R76") (pin "2") (pinfunction "2_2") (pintype "passive"))
      (node (ref "R77") (pin "2") (pinfunction "2_2") (pintype "passive"))
      (node (ref "R85") (pin "2") (pinfunction "2_2") (pintype "passive"))
      (node (ref "R86") (pin "2") (pinfunction "2_2") (pintype "passive"))
      (node (ref "U8") (pin "14") (pinfunction "GND_14") (pintype "power_in"))
      (node (ref "U8") (pin "27") (pinfunction "GND_27") (pintype "power_in"))
      (node (ref "U8") (pin "31") (pinfunction "GND_31") (pintype "power_in"))
      (node (ref "U8") (pin "40") (pinfunction "GND_40") (pintype "power_in"))
      (node (ref "U8") (pin "42") (pinfunction "GND_42") (pintype "power_in"))
      (node (ref "U8") (pin "44") (pinfunction "GND_44") (pintype "power_in"))
      (node (ref "U8") (pin "45") (pinfunction "GND_45") (pintype "power_in"))
      (node (ref "U8") (pin "48") (pinfunction "GND_48") (pintype "power_in"))
      (node (ref "U8") (pin "49") (pinfunction "GND_49") (pintype "power_in"))
    )
    (net (code "31") (name "GNSS_3V3") (class "Default")
      (node (ref "C52") (pin "1") (pintype "passive"))
      (node (ref "C54") (pin "1") (pintype "passive"))
      (node (ref "R96") (pin "1") (pinfunction "1_1") (pintype "passive"))
      (node (ref "U8") (pin "26") (pinfunction "GNSS_VCC_26") (pintype "power_in"))
    )
    (net (code "32") (name "GSM_4V0") (class "Default")
      (node (ref "C51") (pin "1") (pintype "passive"))
      (node (ref "C53") (pin "1") (pintype "passive"))
      (node (ref "C55") (pin "1") (pintype "passive"))
      (node (ref "C56") (pin "1") (pintype "passive"))
      (node (ref "D9") (pin "1") (pinfunction "K_1") (pintype "passive"))
      (node (ref "U8") (pin "50") (pinfunction "VBAT_50") (pintype "power_in"))
      (node (ref "U8") (pin "51") (pinfunction "VBAT_51") (pintype "power_in"))
    )
    (net (code "33") (name "GSM_VRTC") (class "Default")
      (node (ref "U8") (pin "52") (pinfunction "VRTC_52") (pintype "power_in"))
    )
    (net (code "34") (name "Net-(D10-C)") (class "Default")
      (node (ref "D10") (pin "1") (pinfunction "C_1") (pintype "passive"))
      (node (ref "R73") (pin "1") (pinfunction "1_1") (pintype "passive"))
    )
    (net (code "35") (name "Net-(D11-C)") (class "Default")
      (node (ref "D11") (pin "1") (pinfunction "C_1") (pintype "passive"))
      (node (ref "R78") (pin "1") (pinfunction "1_1") (pintype "passive"))
    )
    (net (code "36") (name "Net-(D12-C3)") (class "Default")
      (node (ref "C62") (pin "2") (pinfunction "2_2") (pintype "passive"))
      (node (ref "D12") (pin "4") (pinfunction "C3_4") (pintype "passive"))
      (node (ref "J17") (pin "C7") (pinfunction "I/O_C7") (pintype "passive"))
      (node (ref "R90") (pin "2") (pinfunction "2_2") (pintype "passive"))
    )
    (net (code "37") (name "Net-(D12-C4)") (class "Default")
      (node (ref "C65") (pin "2") (pinfunction "2_2") (pintype "passive"))
      (node (ref "D12") (pin "5") (pinfunction "C4_5") (pintype "passive"))
      (node (ref "J17") (pin "C3") (pinfunction "CLK_C3") (pintype "passive"))
      (node (ref "R89") (pin "2") (pinfunction "2_2") (pintype "passive"))
    )
    (net (code "38") (name "Net-(D12-C5)") (class "Default")
      (node (ref "C67") (pin "2") (pinfunction "2_2") (pintype "passive"))
      (node (ref "D12") (pin "6") (pinfunction "C5_6") (pintype "passive"))
      (node (ref "J17") (pin "C2") (pinfunction "RESET_C2") (pintype "passive"))
      (node (ref "R88") (pin "2") (pinfunction "2_2") (pintype "passive"))
    )
    (net (code "39") (name "Net-(D13-C2)") (class "Default")
      (node (ref "C68") (pin "2") (pinfunction "2_2") (pintype "passive"))
      (node (ref "D13") (pin "3") (pinfunction "C2_3") (pintype "passive"))
      (node (ref "J18") (pin "C2") (pinfunction "RESET_C2") (pintype "passive"))
      (node (ref "R91") (pin "2") (pinfunction "2_2") (pintype "passive"))
    )
    (net (code "40") (name "Net-(D13-C3)") (class "Default")
      (node (ref "C66") (pin "2") (pinfunction "2_2") (pintype "passive"))
      (node (ref "D13") (pin "4") (pinfunction "C3_4") (pintype "passive"))
      (node (ref "J18") (pin "C3") (pinfunction "CLK_C3") (pintype "passive"))
      (node (ref "R92") (pin "2") (pinfunction "2_2") (pintype "passive"))
    )
    (net (code "41") (name "Net-(D13-C4)") (class "Default")
      (node (ref "C64") (pin "2") (pinfunction "2_2") (pintype "passive"))
      (node (ref "D13") (pin "5") (pinfunction "C4_5") (pintype "passive"))
      (node (ref "J18") (pin "C7") (pinfunction "I/O_C7") (pintype "passive"))
      (node (ref "R93") (pin "2") (pinfunction "2_2") (pintype "passive"))
    )
    (net (code "42") (name "Net-(J15-SIG)") (class "Default")
      (node (ref "C59") (pin "1") (pintype "passive"))
      (node (ref "J15") (pin "1") (pinfunction "SIG_1") (pintype "passive"))
      (node (ref "R87") (pin "1") (pinfunction "1_1") (pintype "passive"))
    )
    (net (code "43") (name "Net-(J16-SIG)") (class "Default")
      (node (ref "C70") (pin "1") (pintype "passive"))
      (node (ref "J16") (pin "1") (pinfunction "SIG_1") (pintype "passive"))
      (node (ref "R94") (pin "1") (pinfunction "1_1") (pintype "passive"))
    )
    (net (code "44") (name "Net-(J19-SIG)") (class "Default")
      (node (ref "C73") (pin "1") (pintype "passive"))
      (node (ref "J19") (pin "1") (pinfunction "SIG_1") (pintype "passive"))
      (node (ref "L2") (pin "1") (pinfunction "1_1") (pintype "passive"))
      (node (ref "R95") (pin "1") (pinfunction "1_1") (pintype "passive"))
    )
    (net (code "45") (name "Net-(L2-Pad2)") (class "Default")
      (node (ref "L2") (pin "2") (pinfunction "2_2") (pintype "passive"))
      (node (ref "R96") (pin "2") (pinfunction "2_2") (pintype "passive"))
    )
    (net (code "46") (name "Net-(Q12-B)") (class "Default")
      (node (ref "Q12") (pin "1") (pinfunction "B_1") (pintype "passive"))
      (node (ref "R69") (pin "2") (pinfunction "2_2") (pintype "passive"))
      (node (ref "R70") (pin "1") (pinfunction "1_1") (pintype "passive"))
    )
    (net (code "47") (name "Net-(Q12-C)") (class "Default")
      (node (ref "Q12") (pin "3") (pinfunction "C_3") (pintype "passive"))
      (node (ref "R73") (pin "2") (pinfunction "2_2") (pintype "passive"))
    )
    (net (code "48") (name "Net-(Q13-B)") (class "Default")
      (node (ref "Q13") (pin "1") (pinfunction "B_1") (pintype "passive"))
      (node (ref "R68") (pin "1") (pinfunction "1_1") (pintype "passive"))
      (node (ref "R71") (pin "1") (pinfunction "1_1") (pintype "passive"))
    )
    (net (code "49") (name "Net-(Q14-B)") (class "Default")
      (node (ref "Q14") (pin "1") (pinfunction "B_1") (pintype "passive"))
      (node (ref "R75") (pin "2") (pinfunction "2_2") (pintype "passive"))
      (node (ref "R76") (pin "1") (pinfunction "1_1") (pintype "passive"))
    )
    (net (code "50") (name "Net-(Q14-C)") (class "Default")
      (node (ref "Q14") (pin "3") (pinfunction "C_3") (pintype "passive"))
      (node (ref "R78") (pin "2") (pinfunction "2_2") (pintype "passive"))
    )
    (net (code "51") (name "SIM1_VCC") (class "Default")
      (node (ref "C60") (pin "2") (pinfunction "2_2") (pintype "passive"))
      (node (ref "C74") (pin "2") (pinfunction "2_2") (pintype "passive"))
      (node (ref "D12") (pin "3") (pinfunction "C2_3") (pintype "passive"))
      (node (ref "J17") (pin "C1") (pinfunction "VCC_C1") (pintype "passive"))
      (node (ref "U8") (pin "18") (pinfunction "SIM1_VDD_18") (pintype "power_in"))
    )
    (net (code "52") (name "SIM2_VCC") (class "Default")
      (node (ref "C61") (pin "2") (pinfunction "2_2") (pintype "passive"))
      (node (ref "C75") (pin "2") (pinfunction "2_2") (pintype "passive"))
      (node (ref "D13") (pin "6") (pinfunction "C5_6") (pintype "passive"))
      (node (ref "J18") (pin "C1") (pinfunction "VCC_C1") (pintype "passive"))
      (node (ref "U8") (pin "13") (pinfunction "SIM2_VDD_13") (pintype "power_in"))
    )
    (net (code "53") (name "SIM_GND") (class "Default")
      (node (ref "C69") (pin "2") (pinfunction "2_2") (pintype "passive"))
      (node (ref "C71") (pin "2") (pinfunction "2_2") (pintype "passive"))
      (node (ref "C74") (pin "1") (pinfunction "1_1") (pintype "passive"))
      (node (ref "C75") (pin "1") (pinfunction "1_1") (pintype "passive"))
      (node (ref "D12") (pin "1") (pinfunction "C1_1") (pintype "passive"))
      (node (ref "D13") (pin "1") (pinfunction "C1_1") (pintype "passive"))
      (node (ref "J17") (pin "C5") (pinfunction "GND_C5") (pintype "passive"))
      (node (ref "J18") (pin "C5") (pinfunction "GND_C5") (pintype "passive"))
      (node (ref "U8") (pin "16") (pinfunction "SIM_GND_16") (pintype "power_in"))
    )
    (net (code "54") (name "unconnected-(J17-VPP-PadC6)") (class "Default")
      (node (ref "J17") (pin "C6") (pinfunction "VPP_C6") (pintype "passive+no_connect"))
    )
    (net (code "55") (name "unconnected-(J18-VPP-PadC6)") (class "Default")
      (node (ref "J18") (pin "C6") (pinfunction "VPP_C6") (pintype "passive+no_connect"))
    )
    (net (code "56") (name "unconnected-(U8-ADC-Pad6)") (class "Default")
      (node (ref "U8") (pin "6") (pinfunction "ADC_6") (pintype "input+no_connect"))
    )
    (net (code "57") (name "unconnected-(U8-CTS-Pad38)") (class "Default")
      (node (ref "U8") (pin "38") (pinfunction "CTS_38") (pintype "output+no_connect"))
    )
    (net (code "58") (name "unconnected-(U8-DBG_RXD-Pad30)") (class "Default")
      (node (ref "U8") (pin "30") (pinfunction "DBG_RXD_30") (pintype "input+no_connect"))
    )
    (net (code "59") (name "unconnected-(U8-DBG_TXD-Pad29)") (class "Default")
      (node (ref "U8") (pin "29") (pinfunction "DBG_TXD_29") (pintype "output+no_connect"))
    )
    (net (code "60") (name "unconnected-(U8-DCD-Pad36)") (class "Default")
      (node (ref "U8") (pin "36") (pinfunction "DCD_36") (pintype "output+no_connect"))
    )
    (net (code "61") (name "unconnected-(U8-LOUDSPKN-Pad53)") (class "Default")
      (node (ref "U8") (pin "53") (pinfunction "LOUDSPKN_53") (pintype "output+no_connect"))
    )
    (net (code "62") (name "unconnected-(U8-LOUDSPKP-Pad54)") (class "Default")
      (node (ref "U8") (pin "54") (pinfunction "LOUDSPKP_54") (pintype "output+no_connect"))
    )
    (net (code "63") (name "unconnected-(U8-MICN-Pad2)") (class "Default")
      (node (ref "U8") (pin "2") (pinfunction "MICN_2") (pintype "input+no_connect"))
    )
    (net (code "64") (name "unconnected-(U8-MICP-Pad1)") (class "Default")
      (node (ref "U8") (pin "1") (pinfunction "MICP_1") (pintype "input+no_connect"))
    )
    (net (code "65") (name "unconnected-(U8-PCM_CLK-Pad59)") (class "Default")
      (node (ref "U8") (pin "59") (pinfunction "PCM_CLK_59") (pintype "output+no_connect"))
    )
    (net (code "66") (name "unconnected-(U8-PCM_IN-Pad62)") (class "Default")
      (node (ref "U8") (pin "62") (pinfunction "PCM_IN_62") (pintype "input+no_connect"))
    )
    (net (code "67") (name "unconnected-(U8-PCM_OUT-Pad60)") (class "Default")
      (node (ref "U8") (pin "60") (pinfunction "PCM_OUT_60") (pintype "output+no_connect"))
    )
    (net (code "68") (name "unconnected-(U8-PCM_SYNC-Pad61)") (class "Default")
      (node (ref "U8") (pin "61") (pinfunction "PCM_SYNC_61") (pintype "output+no_connect"))
    )
    (net (code "69") (name "unconnected-(U8-RESERVED-Pad46)") (class "Default")
      (node (ref "U8") (pin "46") (pinfunction "RESERVED_46") (pintype "bidirectional+no_connect"))
    )
    (net (code "70") (name "unconnected-(U8-RESERVED-Pad55)") (class "Default")
      (node (ref "U8") (pin "55") (pinfunction "RESERVED_55") (pintype "bidirectional+no_connect"))
    )
    (net (code "71") (name "unconnected-(U8-RESERVED-Pad56)") (class "Default")
      (node (ref "U8") (pin "56") (pinfunction "RESERVED_56") (pintype "bidirectional+no_connect"))
    )
    (net (code "72") (name "unconnected-(U8-RESERVED-Pad57)") (class "Default")
      (node (ref "U8") (pin "57") (pinfunction "RESERVED_57") (pintype "bidirectional+no_connect"))
    )
    (net (code "73") (name "unconnected-(U8-RESERVED-Pad58)") (class "Default")
      (node (ref "U8") (pin "58") (pinfunction "RESERVED_58") (pintype "bidirectional+no_connect"))
    )
    (net (code "74") (name "unconnected-(U8-RESERVED-Pad63)") (class "Default")
      (node (ref "U8") (pin "63") (pinfunction "RESERVED_63") (pintype "bidirectional+no_connect"))
    )
    (net (code "75") (name "unconnected-(U8-RESERVED-Pad64)") (class "Default")
      (node (ref "U8") (pin "64") (pinfunction "RESERVED_64") (pintype "bidirectional+no_connect"))
    )
    (net (code "76") (name "unconnected-(U8-RESERVED-Pad65)") (class "Default")
      (node (ref "U8") (pin "65") (pinfunction "RESERVED_65") (pintype "bidirectional+no_connect"))
    )
    (net (code "77") (name "unconnected-(U8-RESERVED-Pad66)") (class "Default")
      (node (ref "U8") (pin "66") (pinfunction "RESERVED_66") (pintype "bidirectional+no_connect"))
    )
    (net (code "78") (name "unconnected-(U8-RESERVED-Pad67)") (class "Default")
      (node (ref "U8") (pin "67") (pinfunction "RESERVED_67") (pintype "bidirectional+no_connect"))
    )
    (net (code "79") (name "unconnected-(U8-RESERVED-Pad68)") (class "Default")
      (node (ref "U8") (pin "68") (pinfunction "RESERVED_68") (pintype "bidirectional+no_connect"))
    )
    (net (code "80") (name "unconnected-(U8-RTS-Pad39)") (class "Default")
      (node (ref "U8") (pin "39") (pinfunction "RTS_39") (pintype "input+no_connect"))
    )
    (net (code "81") (name "unconnected-(U8-SD_CLK-Pad8)") (class "Default")
      (node (ref "U8") (pin "8") (pinfunction "SD_CLK_8") (pintype "output+no_connect"))
    )
    (net (code "82") (name "unconnected-(U8-SD_CMD-Pad7)") (class "Default")
      (node (ref "U8") (pin "7") (pinfunction "SD_CMD_7") (pintype "output+no_connect"))
    )
    (net (code "83") (name "unconnected-(U8-SD_DATA-Pad9)") (class "Default")
      (node (ref "U8") (pin "9") (pinfunction "SD_DATA_9") (pintype "bidirectional+no_connect"))
    )
    (net (code "84") (name "unconnected-(U8-SPKN-Pad4)") (class "Default")
      (node (ref "U8") (pin "4") (pinfunction "SPKN_4") (pintype "output+no_connect"))
    )
    (net (code "85") (name "unconnected-(U8-SPKP-Pad3)") (class "Default")
      (node (ref "U8") (pin "3") (pinfunction "SPKP_3") (pintype "output+no_connect"))
    )
    (net (code "86") (name "unconnected-(U8-VDD_EXT-Pad43)") (class "Default")
      (node (ref "U8") (pin "43") (pinfunction "VDD_EXT_43") (pintype "power_in+no_connect"))
    )
  )
)
